# 17_Voltage_Regulators.net
KiCad netlist of a schematic drawn in Altium Designer
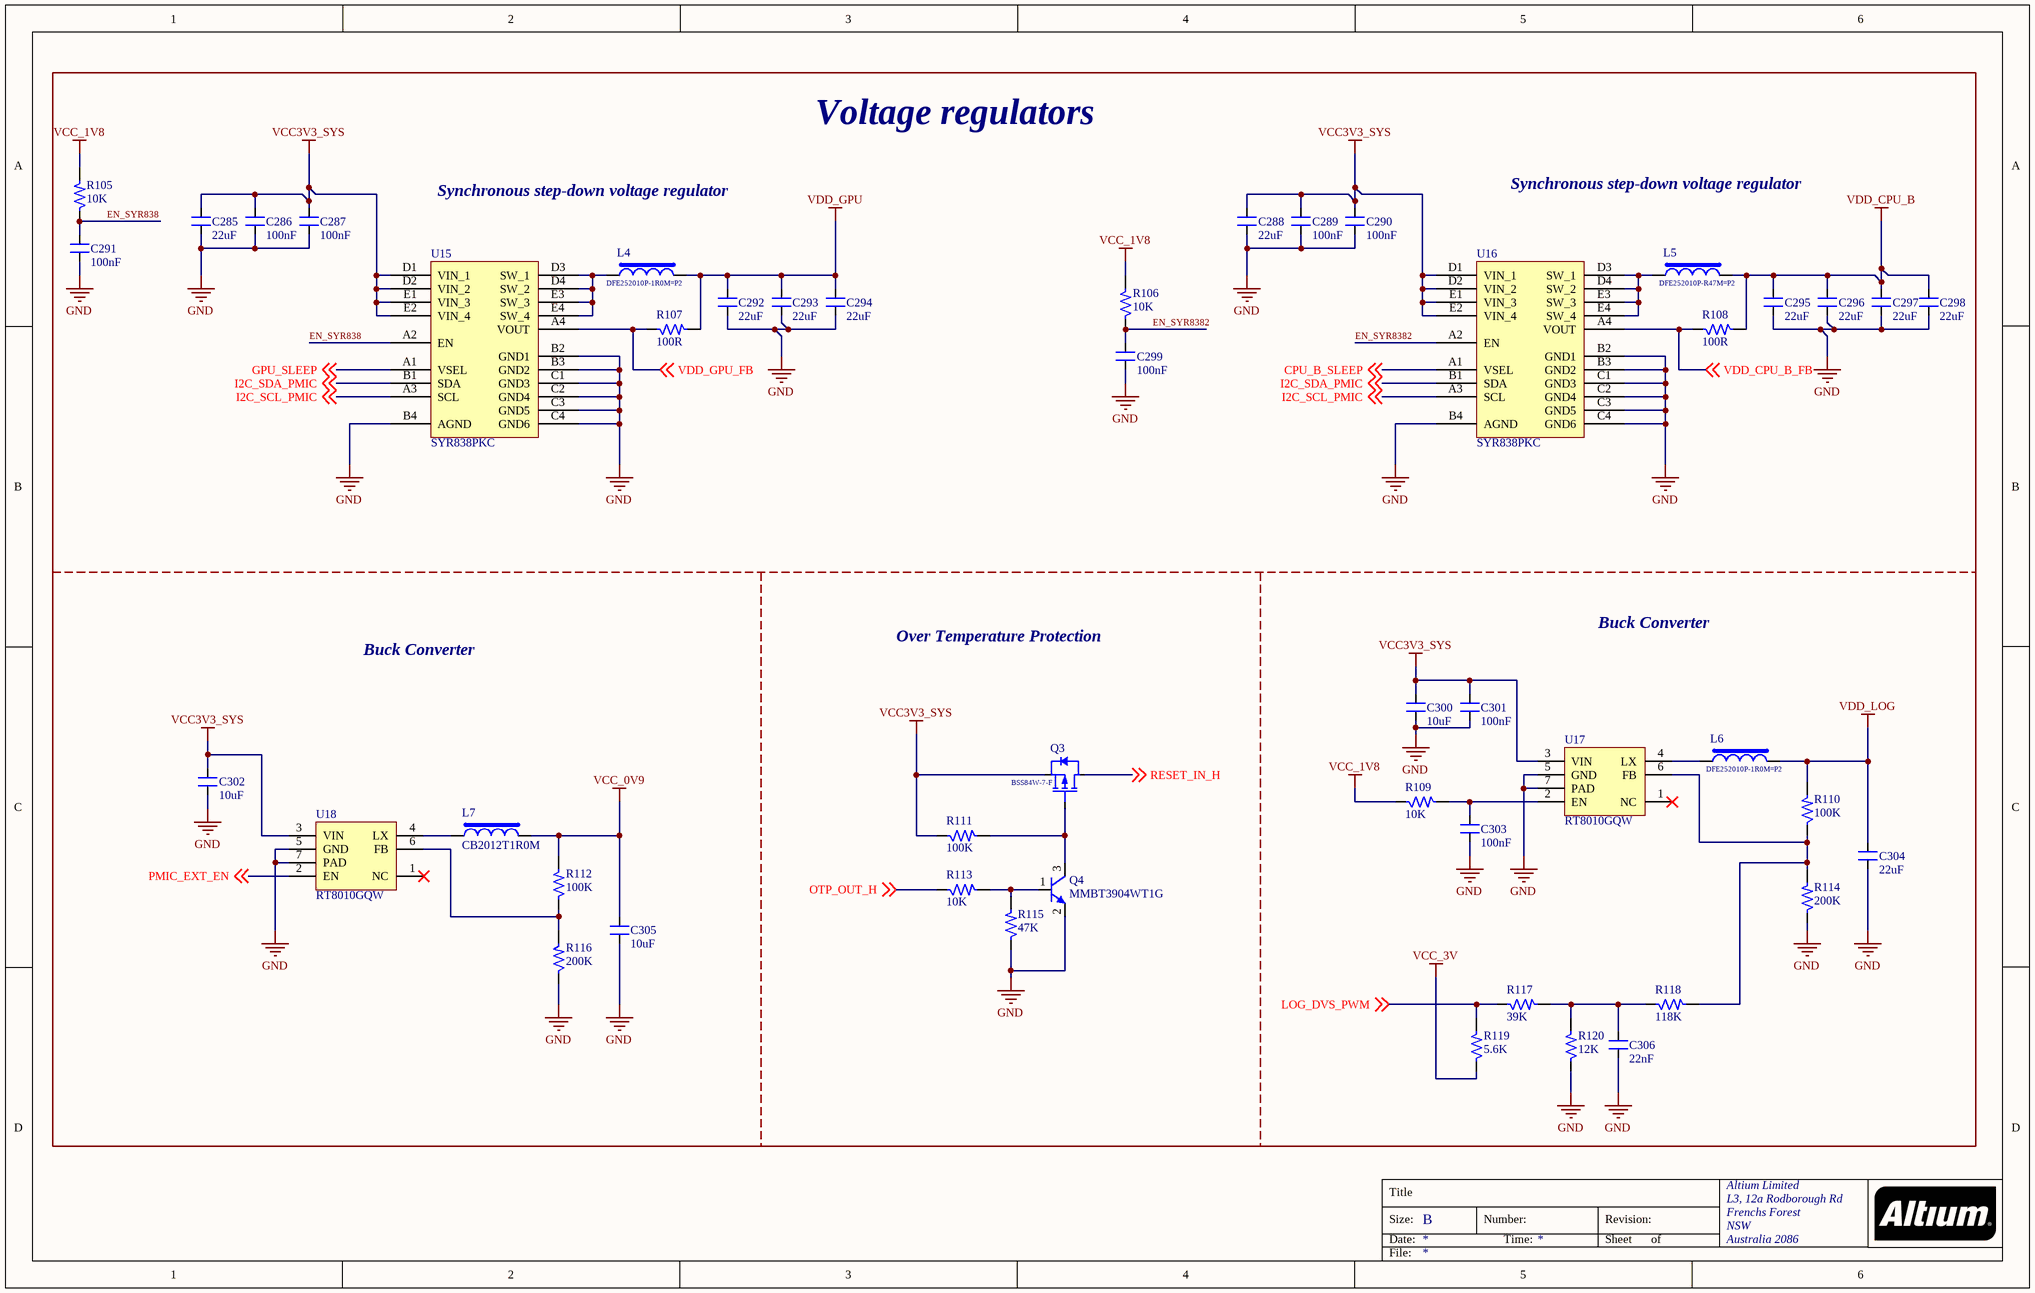
[diagram p0: [17] Voltage_Regulators.SchDoc]

(export (version "E")
  (design (tool "Eeschema 10.0.6"))
  (components
    (comp (ref "C285")
      (value "22uF")
      (footprint "CAP_0402")
      (description "22µF ±20% 6.3V Ceramic Capacitor X5R 0402 (1005 Metric)")
      (fields
        (field (name "MANUFACTURER") "Murata Electronics")
        (field (name "MANUFACTURER PART NUMBER") "CL05A226MQ5N6J8")
      )
      (libsource (lib "EsteemPCB_SOM_Course_intlib") (part "CAP_22uF-6.3V-20%-0402"))
    )
    (comp (ref "C286")
      (value "100nF")
      (footprint "CAP_0402")
      (description "0.1µF ±10% 25V Ceramic Capacitor X7R 0402 (1005 Metric)")
      (fields
        (field (name "MANUFACTURER") "Walsin Technology Corporation")
        (field (name "MANUFACTURER PART NUMBER") "0402B104K250CT")
      )
      (libsource (lib "EsteemPCB_SOM_Course_intlib") (part "CAP_100nF-25V-10%-0402"))
    )
    (comp (ref "C287")
      (value "100nF")
      (footprint "CAP_0402")
      (description "0.1µF ±10% 25V Ceramic Capacitor X7R 0402 (1005 Metric)")
      (fields
        (field (name "MANUFACTURER") "Walsin Technology Corporation")
        (field (name "MANUFACTURER PART NUMBER") "0402B104K250CT")
      )
      (libsource (lib "EsteemPCB_SOM_Course_intlib") (part "CAP_100nF-25V-10%-0402"))
    )
    (comp (ref "C288")
      (value "22uF")
      (footprint "CAP_0402")
      (description "22µF ±20% 6.3V Ceramic Capacitor X5R 0402 (1005 Metric)")
      (fields
        (field (name "MANUFACTURER") "Murata Electronics")
        (field (name "MANUFACTURER PART NUMBER") "CL05A226MQ5N6J8")
      )
      (libsource (lib "EsteemPCB_SOM_Course_intlib") (part "CAP_22uF-6.3V-20%-0402"))
    )
    (comp (ref "C289")
      (value "100nF")
      (footprint "CAP_0402")
      (description "0.1µF ±10% 25V Ceramic Capacitor X7R 0402 (1005 Metric)")
      (fields
        (field (name "MANUFACTURER") "Walsin Technology Corporation")
        (field (name "MANUFACTURER PART NUMBER") "0402B104K250CT")
      )
      (libsource (lib "EsteemPCB_SOM_Course_intlib") (part "CAP_100nF-25V-10%-0402"))
    )
    (comp (ref "C290")
      (value "100nF")
      (footprint "CAP_0402")
      (description "0.1µF ±10% 25V Ceramic Capacitor X7R 0402 (1005 Metric)")
      (fields
        (field (name "MANUFACTURER") "Walsin Technology Corporation")
        (field (name "MANUFACTURER PART NUMBER") "0402B104K250CT")
      )
      (libsource (lib "EsteemPCB_SOM_Course_intlib") (part "CAP_100nF-25V-10%-0402"))
    )
    (comp (ref "C291")
      (value "100nF")
      (footprint "CAP_0402")
      (description "0.1µF ±10% 25V Ceramic Capacitor X7R 0402 (1005 Metric)")
      (fields
        (field (name "MANUFACTURER") "Walsin Technology Corporation")
        (field (name "MANUFACTURER PART NUMBER") "0402B104K250CT")
      )
      (libsource (lib "EsteemPCB_SOM_Course_intlib") (part "CAP_100nF-25V-10%-0402"))
    )
    (comp (ref "C292")
      (value "22uF")
      (footprint "CAP_0402")
      (description "22µF ±20% 6.3V Ceramic Capacitor X5R 0402 (1005 Metric)")
      (fields
        (field (name "MANUFACTURER") "Murata Electronics")
        (field (name "MANUFACTURER PART NUMBER") "CL05A226MQ5N6J8")
      )
      (libsource (lib "EsteemPCB_SOM_Course_intlib") (part "CAP_22uF-6.3V-20%-0402"))
    )
    (comp (ref "C293")
      (value "22uF")
      (footprint "CAP_0402")
      (description "22µF ±20% 6.3V Ceramic Capacitor X5R 0402 (1005 Metric)")
      (fields
        (field (name "MANUFACTURER") "Murata Electronics")
        (field (name "MANUFACTURER PART NUMBER") "CL05A226MQ5N6J8")
      )
      (libsource (lib "EsteemPCB_SOM_Course_intlib") (part "CAP_22uF-6.3V-20%-0402"))
    )
    (comp (ref "C294")
      (value "22uF")
      (footprint "CAP_0402")
      (description "22µF ±20% 6.3V Ceramic Capacitor X5R 0402 (1005 Metric)")
      (fields
        (field (name "MANUFACTURER") "Murata Electronics")
        (field (name "MANUFACTURER PART NUMBER") "CL05A226MQ5N6J8")
      )
      (libsource (lib "EsteemPCB_SOM_Course_intlib") (part "CAP_22uF-6.3V-20%-0402"))
    )
    (comp (ref "C295")
      (value "22uF")
      (footprint "CAP_0402")
      (description "22µF ±20% 6.3V Ceramic Capacitor X5R 0402 (1005 Metric)")
      (fields
        (field (name "MANUFACTURER") "Murata Electronics")
        (field (name "MANUFACTURER PART NUMBER") "CL05A226MQ5N6J8")
      )
      (libsource (lib "EsteemPCB_SOM_Course_intlib") (part "CAP_22uF-6.3V-20%-0402"))
    )
    (comp (ref "C296")
      (value "22uF")
      (footprint "CAP_0402")
      (description "22µF ±20% 6.3V Ceramic Capacitor X5R 0402 (1005 Metric)")
      (fields
        (field (name "MANUFACTURER") "Murata Electronics")
        (field (name "MANUFACTURER PART NUMBER") "CL05A226MQ5N6J8")
      )
      (libsource (lib "EsteemPCB_SOM_Course_intlib") (part "CAP_22uF-6.3V-20%-0402"))
    )
    (comp (ref "C297")
      (value "22uF")
      (footprint "CAP_0402")
      (description "22µF ±20% 6.3V Ceramic Capacitor X5R 0402 (1005 Metric)")
      (fields
        (field (name "MANUFACTURER") "Murata Electronics")
        (field (name "MANUFACTURER PART NUMBER") "CL05A226MQ5N6J8")
      )
      (libsource (lib "EsteemPCB_SOM_Course_intlib") (part "CAP_22uF-6.3V-20%-0402"))
    )
    (comp (ref "C298")
      (value "22uF")
      (footprint "CAP_0402")
      (description "22µF ±20% 6.3V Ceramic Capacitor X5R 0402 (1005 Metric)")
      (fields
        (field (name "MANUFACTURER") "Murata Electronics")
        (field (name "MANUFACTURER PART NUMBER") "CL05A226MQ5N6J8")
      )
      (libsource (lib "EsteemPCB_SOM_Course_intlib") (part "CAP_22uF-6.3V-20%-0402"))
    )
    (comp (ref "C299")
      (value "100nF")
      (footprint "CAP_0402")
      (description "0.1µF ±10% 25V Ceramic Capacitor X7R 0402 (1005 Metric)")
      (fields
        (field (name "MANUFACTURER") "Walsin Technology Corporation")
        (field (name "MANUFACTURER PART NUMBER") "0402B104K250CT")
      )
      (libsource (lib "EsteemPCB_SOM_Course_intlib") (part "CAP_100nF-25V-10%-0402"))
    )
    (comp (ref "C300")
      (value "10uF")
      (footprint "CAP_0402")
      (description "10µF ±20% 10V Ceramic Capacitor X5R 0402 (1005 Metric)")
      (fields
        (field (name "MANUFACTURER PART NUMBER") "CL05A106MP5NUNC")
        (field (name "MANUFACTURER") "Samsung Electro-Mechanics")
      )
      (libsource (lib "EsteemPCB_SOM_Course_intlib") (part "CAP_10uF-10V-20%-0402"))
    )
    (comp (ref "C301")
      (value "100nF")
      (footprint "CAP_0402")
      (description "0.1µF ±10% 10V Ceramic Capacitor X7R 0402 (1005 Metric)")
      (fields
        (field (name "MANUFACTURER") "Yageo")
        (field (name "MANUFACTURER PART NUMBER") "CC0402KRX7R6BB104")
      )
      (libsource (lib "EsteemPCB_SOM_Course_intlib") (part "CAP_100nF-10V-10%-0402"))
    )
    (comp (ref "C302")
      (value "10uF")
      (footprint "CAP_0402")
      (description "10µF ±20% 10V Ceramic Capacitor X5R 0402 (1005 Metric)")
      (fields
        (field (name "MANUFACTURER PART NUMBER") "CL05A106MP5NUNC")
        (field (name "MANUFACTURER") "Samsung Electro-Mechanics")
      )
      (libsource (lib "EsteemPCB_SOM_Course_intlib") (part "CAP_10uF-10V-20%-0402"))
    )
    (comp (ref "C303")
      (value "100nF")
      (footprint "CAP_0402")
      (description "0.1µF ±10% 10V Ceramic Capacitor X7R 0402 (1005 Metric)")
      (fields
        (field (name "MANUFACTURER") "Yageo")
        (field (name "MANUFACTURER PART NUMBER") "CC0402KRX7R6BB104")
      )
      (libsource (lib "EsteemPCB_SOM_Course_intlib") (part "CAP_100nF-10V-10%-0402"))
    )
    (comp (ref "C304")
      (value "22uF")
      (footprint "CAP_0402")
      (description "22µF ±20% 6.3V Ceramic Capacitor X5R 0402 (1005 Metric)")
      (fields
        (field (name "MANUFACTURER") "Murata Electronics")
        (field (name "MANUFACTURER PART NUMBER") "CL05A226MQ5N6J8")
      )
      (libsource (lib "EsteemPCB_SOM_Course_intlib") (part "CAP_22uF-6.3V-20%-0402"))
    )
    (comp (ref "C305")
      (value "10uF")
      (footprint "CAP_0402")
      (description "10µF ±20% 10V Ceramic Capacitor X5R 0402 (1005 Metric)")
      (fields
        (field (name "MANUFACTURER PART NUMBER") "CL05A106MP5NUNC")
        (field (name "MANUFACTURER") "Samsung Electro-Mechanics")
      )
      (libsource (lib "EsteemPCB_SOM_Course_intlib") (part "CAP_10uF-10V-20%-0402"))
    )
    (comp (ref "C306")
      (value "22nF")
      (footprint "CAP_0402")
      (description "0.022µF ±10% 10V Ceramic Capacitor X7R 0402 (1005 Metric)")
      (fields
        (field (name "MANUFACTURER") "Samsung Electro-Mechanics")
        (field (name "MANUFACTURER PART NUMBER") "CL05B223KP5NNNC")
      )
      (libsource (lib "EsteemPCB_SOM_Course_intlib") (part "CAP_22nF-10V-10%-0402"))
    )
    (comp (ref "L4")
      (value "DFE252010P-1R0M=P2")
      (footprint "IND_1008")
      (description "1µH Shielded Wirewound Inductor 3.8A 54mOhm Max 1008 (2520 Metric)")
      (fields (field (name "MANUFACTURER") "Murata Electronics"))
      (libsource (lib "EsteemPCB_SOM_Course_intlib") (part "IND_1uH-3.8A-20%-1008"))
    )
    (comp (ref "L5")
      (value "DFE252010P-R47M=P2")
      (footprint "IND_1008")
      (description "470nH Shielded Wirewound Inductor 5A 35mOhm Max 1008 (2520 Metric)")
      (fields (field (name "MANUFACTURER") "Murata Electronics"))
      (libsource (lib "EsteemPCB_SOM_Course_intlib") (part "IND_470nH-5A-20%-1008"))
    )
    (comp (ref "L6")
      (value "DFE252010P-1R0M=P2")
      (footprint "IND_1008")
      (description "1µH Shielded Wirewound Inductor 3.8A 54mOhm Max 1008 (2520 Metric)")
      (fields (field (name "MANUFACTURER") "Murata Electronics"))
      (libsource (lib "EsteemPCB_SOM_Course_intlib") (part "IND_1uH-3.8A-20%-1008"))
    )
    (comp (ref "L7")
      (value "CB2012T1R0M")
      (footprint "IND_0805")
      (description "1uH ±20% 500mA 150mΩ 0805 Inductors (SMD) RoHS")
      (fields (field (name "MANUFACTURER") "Taiyo Yuden"))
      (libsource (lib "EsteemPCB_SOM_Course_intlib") (part "IND_1uF-0.5A-20%-0805"))
    )
    (comp (ref "Q3")
      (value "BSS84W-7-F")
      (footprint "SOT-323-3")
      (description "P-Channel 50V 130mA (Ta) 200mW (Ta) Surface Mount SOT-323")
      (fields (field (name "MANUFACTURER") "Diodes Incorporated"))
      (libsource (lib "EsteemPCB_SOM_Course_intlib") (part "MOSFET-P_50V-130mA-SOT-323"))
    )
    (comp (ref "Q4")
      (value "MMBT3904WT1G")
      (footprint "SOT-323-3")
      (description "Bipolar (BJT) Transistor NPN 40V 200mA 300MHz 150mW Surface Mount SC-70-3 (SOT323)")
      (fields (field (name "MANUFACTURER") "ON Semiconductor"))
      (libsource (lib "EsteemPCB_SOM_Course_intlib") (part "TRAN-NPN_40V-200mA-SOT323"))
    )
    (comp (ref "R105")
      (value "10K")
      (footprint "RES_0402")
      (description "10 kOhms ±1% 0.1W, 1/10W Chip Resistor 0402 (1005 Metric) Anti-Sulfur Thin Film")
      (fields
        (field (name "MANUFACTURER") "Vishay Beyschlag/Draloric/BC Components")
        (field (name "MANUFACTURER PART NUMBER") "MCS04020C1002FE000")
      )
      (libsource (lib "EsteemPCB_SOM_Course_intlib") (part "RES_10K-0.1W-1%-0402"))
    )
    (comp (ref "R106")
      (value "10K")
      (footprint "RES_0402")
      (description "10 kOhms ±1% 0.1W, 1/10W Chip Resistor 0402 (1005 Metric) Anti-Sulfur Thin Film")
      (fields
        (field (name "MANUFACTURER") "Vishay Beyschlag/Draloric/BC Components")
        (field (name "MANUFACTURER PART NUMBER") "MCS04020C1002FE000")
      )
      (libsource (lib "EsteemPCB_SOM_Course_intlib") (part "RES_10K-0.1W-1%-0402"))
    )
    (comp (ref "R107")
      (value "100R")
      (footprint "RES_0402")
      (fields
        (field (name "MANUFACTURER") "KOA Speer Electronics, Inc.")
        (field (name "MANUFACTURER PART NUMBER") "RK73H1ETTP1000F")
      )
      (libsource (lib "EsteemPCB_SOM_Course_intlib") (part "RES_100R-0.1W-1%-0402"))
    )
    (comp (ref "R108")
      (value "100R")
      (footprint "RES_0402")
      (fields
        (field (name "MANUFACTURER") "KOA Speer Electronics, Inc.")
        (field (name "MANUFACTURER PART NUMBER") "RK73H1ETTP1000F")
      )
      (libsource (lib "EsteemPCB_SOM_Course_intlib") (part "RES_100R-0.1W-1%-0402"))
    )
    (comp (ref "R109")
      (value "10K")
      (footprint "RES_0402")
      (description "10 kOhms ±1% 0.1W, 1/10W Chip Resistor 0402 (1005 Metric) Anti-Sulfur Thin Film")
      (fields
        (field (name "MANUFACTURER") "Vishay Beyschlag/Draloric/BC Components")
        (field (name "MANUFACTURER PART NUMBER") "MCS04020C1002FE000")
      )
      (libsource (lib "EsteemPCB_SOM_Course_intlib") (part "RES_10K-0.1W-1%-0402"))
    )
    (comp (ref "R110")
      (value "100K")
      (footprint "RES_0402")
      (description "100 kOhms ±1% 0.1W, 1/10W Chip Resistor 0402 (1005 Metric) Anti-Sulfur Thin Film")
      (fields
        (field (name "MANUFACTURER") "Vishay Beyschlag/Draloric/BC Components")
        (field (name "MANUFACTURER PART NUMBER") "MCS04020C1003FE000")
      )
      (libsource (lib "EsteemPCB_SOM_Course_intlib") (part "RES_100K-0.1W-1%-0402"))
    )
    (comp (ref "R111")
      (value "100K")
      (footprint "RES_0402")
      (description "100 kOhms ±1% 0.1W, 1/10W Chip Resistor 0402 (1005 Metric) Anti-Sulfur Thin Film")
      (fields
        (field (name "MANUFACTURER") "Vishay Beyschlag/Draloric/BC Components")
        (field (name "MANUFACTURER PART NUMBER") "MCS04020C1003FE000")
      )
      (libsource (lib "EsteemPCB_SOM_Course_intlib") (part "RES_100K-0.1W-1%-0402"))
    )
    (comp (ref "R112")
      (value "100K")
      (footprint "RES_0402")
      (description "100 kOhms ±1% 0.1W, 1/10W Chip Resistor 0402 (1005 Metric) Anti-Sulfur Thin Film")
      (fields
        (field (name "MANUFACTURER") "Vishay Beyschlag/Draloric/BC Components")
        (field (name "MANUFACTURER PART NUMBER") "MCS04020C1003FE000")
      )
      (libsource (lib "EsteemPCB_SOM_Course_intlib") (part "RES_100K-0.1W-1%-0402"))
    )
    (comp (ref "R113")
      (value "10K")
      (footprint "RES_0402")
      (description "10 kOhms ±1% 0.1W, 1/10W Chip Resistor 0402 (1005 Metric) Anti-Sulfur Thin Film")
      (fields
        (field (name "MANUFACTURER") "Vishay Beyschlag/Draloric/BC Components")
        (field (name "MANUFACTURER PART NUMBER") "MCS04020C1002FE000")
      )
      (libsource (lib "EsteemPCB_SOM_Course_intlib") (part "RES_10K-0.1W-1%-0402"))
    )
    (comp (ref "R114")
      (value "200K")
      (footprint "RES_0402")
      (description "200 kOhms ±1% 0.1W, 1/10W Chip Resistor 0402 (1005 Metric) Automotive AEC-Q200 Thick Film")
      (fields
        (field (name "MANUFACTURER") "Panasonic Electronic Components")
        (field (name "MANUFACTURER PART NUMBER") "ERJ-2RKF2003X")
      )
      (libsource (lib "EsteemPCB_SOM_Course_intlib") (part "RES_200K-0.1W-1%-0402"))
    )
    (comp (ref "R115")
      (value "47K")
      (footprint "RES_0402")
      (description "47 kOhms ±1% 0.1W, 1/10W Chip Resistor 0402 (1005 Metric) Automotive AEC-Q200 Thick Film")
      (fields
        (field (name "MANUFACTURER") "Panasonic Electronic Components")
        (field (name "MANUFACTURER PART NUMBER") "ERJ-2RKF4702X")
      )
      (libsource (lib "EsteemPCB_SOM_Course_intlib") (part "RES_47K-0.1W-1%-0402"))
    )
    (comp (ref "R116")
      (value "200K")
      (footprint "RES_0402")
      (description "200 kOhms ±1% 0.1W, 1/10W Chip Resistor 0402 (1005 Metric) Automotive AEC-Q200 Thick Film")
      (fields
        (field (name "MANUFACTURER") "Panasonic Electronic Components")
        (field (name "MANUFACTURER PART NUMBER") "ERJ-2RKF2003X")
      )
      (libsource (lib "EsteemPCB_SOM_Course_intlib") (part "RES_200K-0.1W-1%-0402"))
    )
    (comp (ref "R117")
      (value "39K")
      (footprint "RES_0402")
      (fields
        (field (name "MANUFACTURER") "KOA Speer Electronics, Inc.")
        (field (name "MANUFACTURER PART NUMBER") "RK73H1ETTP3902F")
      )
      (libsource (lib "EsteemPCB_SOM_Course_intlib") (part "RES_39K-0.1W-1%-0402"))
    )
    (comp (ref "R118")
      (value "118K")
      (footprint "RES_0402")
      (fields
        (field (name "MANUFACTURER") "KOA Speer Electronics, Inc.")
        (field (name "MANUAFCTURER PART NUMBER") "RK73H1ETTP1183F")
      )
      (libsource (lib "EsteemPCB_SOM_Course_intlib") (part "RES_118K-0.1W-1%-0402"))
    )
    (comp (ref "R119")
      (value "5.6K")
      (footprint "RES_0402")
      (fields
        (field (name "MANUFACTURER") "KOA Speer Electronics, Inc.")
        (field (name "MANUFACTURER PART NUMBER") "RK73H1ETTP5601F")
      )
      (libsource (lib "EsteemPCB_SOM_Course_intlib") (part "RES_5.6K-0.1W-1%-0402"))
    )
    (comp (ref "R120")
      (value "12K")
      (footprint "RES_0402")
      (description "12 kOhms ±1% 0.1W, 1/10W Chip Resistor 0402 (1005 Metric) Anti-Sulfur Thin Film")
      (fields
        (field (name "MANUFACTURER") "Vishay Beyschlag/Draloric/BC Components")
        (field (name "MANUFACTURER PART NUMBER") "MCS04020C1202FE000")
      )
      (libsource (lib "EsteemPCB_SOM_Course_intlib") (part "RES_12K-0.1W-1%-0402"))
    )
    (comp (ref "U15")
      (value "SYR838PKC")
      (footprint "CSP20_15.7_100x84_SMD")
      (description "Step-Down Positive Programmable 1 6A 2.4MHz CSP1.56*1.96-20 DC-DC Converters RoHS")
      (fields (field (name "MANUFACTURER") "Silergy Corp"))
      (libsource (lib "EsteemPCB_SOM_Course_intlib") (part "IC_SYR838PKC"))
    )
    (comp (ref "U16")
      (value "SYR838PKC")
      (footprint "CSP20_15.7_100x84_SMD")
      (description "Step-Down Positive Programmable 1 6A 2.4MHz CSP1.56*1.96-20 DC-DC Converters RoHS")
      (fields (field (name "MANUFACTURER") "Silergy Corp"))
      (libsource (lib "EsteemPCB_SOM_Course_intlib") (part "IC_SYR838PKC"))
    )
    (comp (ref "U17")
      (value "RT8010GQW")
      (footprint "WDFN-6_26_133X100_SMD")
      (description "Buck Switching Regulator IC Positive Adjustable 0.6V 1 Output 1A 6-WDFN Exposed Pad")
      (fields (field (name "MANUFACTURER") "Richtek USA Inc."))
      (libsource (lib "EsteemPCB_SOM_Course_intlib") (part "REG-ADJ_5.5V-5.5V-1A-6-WDFN"))
    )
    (comp (ref "U18")
      (value "RT8010GQW")
      (footprint "WDFN-6_26_133X100_SMD")
      (description "Buck Switching Regulator IC Positive Adjustable 0.6V 1 Output 1A 6-WDFN Exposed Pad")
      (fields (field (name "MANUFACTURER") "Richtek USA Inc."))
      (libsource (lib "EsteemPCB_SOM_Course_intlib") (part "REG-ADJ_5.5V-5.5V-1A-6-WDFN"))
    )
  )
  (nets
    (net (code "1") (name "/EN_SYR838") (class "Default")
      (node (ref "C291") (pin "2") (pinfunction "2_2") (pintype "passive"))
      (node (ref "R105") (pin "1") (pinfunction "1_1") (pintype "passive"))
      (node (ref "U15") (pin "A2") (pinfunction "EN_A2") (pintype "passive"))
    )
    (net (code "2") (name "/EN_SYR8382") (class "Default")
      (node (ref "C299") (pin "2") (pinfunction "2_2") (pintype "passive"))
      (node (ref "R106") (pin "1") (pinfunction "1_1") (pintype "passive"))
      (node (ref "U16") (pin "A2") (pinfunction "EN_A2") (pintype "passive"))
    )
    (net (code "3") (name "CPU_B_SLEEP") (class "Default")
      (node (ref "U16") (pin "A1") (pinfunction "VSEL_A1") (pintype "passive"))
    )
    (net (code "4") (name "GND") (class "Default")
      (node (ref "C285") (pin "1") (pinfunction "1_1") (pintype "passive"))
      (node (ref "C286") (pin "1") (pinfunction "1_1") (pintype "passive"))
      (node (ref "C287") (pin "1") (pinfunction "1_1") (pintype "passive"))
      (node (ref "C288") (pin "1") (pinfunction "1_1") (pintype "passive"))
      (node (ref "C289") (pin "1") (pinfunction "1_1") (pintype "passive"))
      (node (ref "C290") (pin "1") (pinfunction "1_1") (pintype "passive"))
      (node (ref "C291") (pin "1") (pinfunction "1_1") (pintype "passive"))
      (node (ref "C292") (pin "1") (pinfunction "1_1") (pintype "passive"))
      (node (ref "C293") (pin "1") (pinfunction "1_1") (pintype "passive"))
      (node (ref "C294") (pin "1") (pinfunction "1_1") (pintype "passive"))
      (node (ref "C295") (pin "1") (pinfunction "1_1") (pintype "passive"))
      (node (ref "C296") (pin "1") (pinfunction "1_1") (pintype "passive"))
      (node (ref "C297") (pin "1") (pinfunction "1_1") (pintype "passive"))
      (node (ref "C298") (pin "1") (pinfunction "1_1") (pintype "passive"))
      (node (ref "C299") (pin "1") (pinfunction "1_1") (pintype "passive"))
      (node (ref "C300") (pin "1") (pinfunction "1_1") (pintype "passive"))
      (node (ref "C301") (pin "1") (pinfunction "1_1") (pintype "passive"))
      (node (ref "C302") (pin "1") (pinfunction "1_1") (pintype "passive"))
      (node (ref "C303") (pin "1") (pinfunction "1_1") (pintype "passive"))
      (node (ref "C304") (pin "1") (pinfunction "1_1") (pintype "passive"))
      (node (ref "C305") (pin "1") (pinfunction "1_1") (pintype "passive"))
      (node (ref "C306") (pin "1") (pinfunction "1_1") (pintype "passive"))
      (node (ref "Q4") (pin "2") (pinfunction "E_2") (pintype "passive"))
      (node (ref "R114") (pin "1") (pinfunction "1_1") (pintype "passive"))
      (node (ref "R115") (pin "1") (pinfunction "1_1") (pintype "passive"))
      (node (ref "R116") (pin "1") (pinfunction "1_1") (pintype "passive"))
      (node (ref "R120") (pin "1") (pinfunction "1_1") (pintype "passive"))
      (node (ref "U15") (pin "B2") (pinfunction "GND1_B2") (pintype "passive"))
      (node (ref "U15") (pin "B3") (pinfunction "GND2_B3") (pintype "passive"))
      (node (ref "U15") (pin "B4") (pinfunction "AGND_B4") (pintype "passive"))
      (node (ref "U15") (pin "C1") (pinfunction "GND3_C1") (pintype "passive"))
      (node (ref "U15") (pin "C2") (pinfunction "GND4_C2") (pintype "passive"))
      (node (ref "U15") (pin "C3") (pinfunction "GND5_C3") (pintype "passive"))
      (node (ref "U15") (pin "C4") (pinfunction "GND6_C4") (pintype "passive"))
      (node (ref "U16") (pin "B2") (pinfunction "GND1_B2") (pintype "passive"))
      (node (ref "U16") (pin "B3") (pinfunction "GND2_B3") (pintype "passive"))
      (node (ref "U16") (pin "B4") (pinfunction "AGND_B4") (pintype "passive"))
      (node (ref "U16") (pin "C1") (pinfunction "GND3_C1") (pintype "passive"))
      (node (ref "U16") (pin "C2") (pinfunction "GND4_C2") (pintype "passive"))
      (node (ref "U16") (pin "C3") (pinfunction "GND5_C3") (pintype "passive"))
      (node (ref "U16") (pin "C4") (pinfunction "GND6_C4") (pintype "passive"))
      (node (ref "U17") (pin "5") (pinfunction "GND_5") (pintype "passive"))
      (node (ref "U17") (pin "7") (pinfunction "PAD_7") (pintype "passive"))
      (node (ref "U18") (pin "5") (pinfunction "GND_5") (pintype "passive"))
      (node (ref "U18") (pin "7") (pinfunction "PAD_7") (pintype "passive"))
    )
    (net (code "5") (name "GPU_SLEEP") (class "Default")
      (node (ref "U15") (pin "A1") (pinfunction "VSEL_A1") (pintype "passive"))
    )
    (net (code "6") (name "I2C_SCL_PMIC") (class "Default")
      (node (ref "U15") (pin "A3") (pinfunction "SCL_A3") (pintype "passive"))
      (node (ref "U16") (pin "A3") (pinfunction "SCL_A3") (pintype "passive"))
    )
    (net (code "7") (name "I2C_SDA_PMIC") (class "Default")
      (node (ref "U15") (pin "B1") (pinfunction "SDA_B1") (pintype "passive"))
      (node (ref "U16") (pin "B1") (pinfunction "SDA_B1") (pintype "passive"))
    )
    (net (code "8") (name "LOG_DVS_PWM") (class "Default")
      (node (ref "R117") (pin "1") (pinfunction "1_1") (pintype "passive"))
      (node (ref "R119") (pin "2") (pinfunction "2_2") (pintype "passive"))
    )
    (net (code "9") (name "Net-(C306-Pad2)") (class "Default")
      (node (ref "C306") (pin "2") (pinfunction "2_2") (pintype "passive"))
      (node (ref "R117") (pin "2") (pinfunction "2_2") (pintype "passive"))
      (node (ref "R118") (pin "1") (pinfunction "1_1") (pintype "passive"))
      (node (ref "R120") (pin "2") (pinfunction "2_2") (pintype "passive"))
    )
    (net (code "10") (name "Net-(Q3-G)") (class "Default")
      (node (ref "Q3") (pin "1") (pinfunction "G_1") (pintype "passive"))
      (node (ref "Q4") (pin "3") (pinfunction "C_3") (pintype "passive"))
      (node (ref "R111") (pin "2") (pinfunction "2_2") (pintype "passive"))
    )
    (net (code "11") (name "Net-(Q4-B)") (class "Default")
      (node (ref "Q4") (pin "1") (pinfunction "B_1") (pintype "passive"))
      (node (ref "R113") (pin "2") (pinfunction "2_2") (pintype "passive"))
      (node (ref "R115") (pin "2") (pinfunction "2_2") (pintype "passive"))
    )
    (net (code "12") (name "Net-(U15-SW_1)") (class "Default")
      (node (ref "L4") (pin "1") (pinfunction "1_1") (pintype "passive"))
      (node (ref "U15") (pin "D3") (pinfunction "SW_1_D3") (pintype "passive"))
      (node (ref "U15") (pin "D4") (pinfunction "SW_2_D4") (pintype "passive"))
      (node (ref "U15") (pin "E3") (pinfunction "SW_3_E3") (pintype "passive"))
      (node (ref "U15") (pin "E4") (pinfunction "SW_4_E4") (pintype "passive"))
    )
    (net (code "13") (name "Net-(U16-SW_1)") (class "Default")
      (node (ref "L5") (pin "1") (pinfunction "1_1") (pintype "passive"))
      (node (ref "U16") (pin "D3") (pinfunction "SW_1_D3") (pintype "passive"))
      (node (ref "U16") (pin "D4") (pinfunction "SW_2_D4") (pintype "passive"))
      (node (ref "U16") (pin "E3") (pinfunction "SW_3_E3") (pintype "passive"))
      (node (ref "U16") (pin "E4") (pinfunction "SW_4_E4") (pintype "passive"))
    )
    (net (code "14") (name "Net-(U17-EN)") (class "Default")
      (node (ref "C303") (pin "2") (pinfunction "2_2") (pintype "passive"))
      (node (ref "R109") (pin "2") (pinfunction "2_2") (pintype "passive"))
      (node (ref "U17") (pin "2") (pinfunction "EN_2") (pintype "passive"))
    )
    (net (code "15") (name "Net-(U17-FB)") (class "Default")
      (node (ref "R110") (pin "1") (pinfunction "1_1") (pintype "passive"))
      (node (ref "R114") (pin "2") (pinfunction "2_2") (pintype "passive"))
      (node (ref "R118") (pin "2") (pinfunction "2_2") (pintype "passive"))
      (node (ref "U17") (pin "6") (pinfunction "FB_6") (pintype "passive"))
    )
    (net (code "16") (name "Net-(U17-LX)") (class "Default")
      (node (ref "L6") (pin "1") (pinfunction "1_1") (pintype "passive"))
      (node (ref "U17") (pin "4") (pinfunction "LX_4") (pintype "passive"))
    )
    (net (code "17") (name "Net-(U18-FB)") (class "Default")
      (node (ref "R112") (pin "1") (pinfunction "1_1") (pintype "passive"))
      (node (ref "R116") (pin "2") (pinfunction "2_2") (pintype "passive"))
      (node (ref "U18") (pin "6") (pinfunction "FB_6") (pintype "passive"))
    )
    (net (code "18") (name "Net-(U18-LX)") (class "Default")
      (node (ref "L7") (pin "1") (pinfunction "1_1") (pintype "passive"))
      (node (ref "U18") (pin "4") (pinfunction "LX_4") (pintype "passive"))
    )
    (net (code "19") (name "OTP_OUT_H") (class "Default")
      (node (ref "R113") (pin "1") (pinfunction "1_1") (pintype "passive"))
    )
    (net (code "20") (name "PMIC_EXT_EN") (class "Default")
      (node (ref "U18") (pin "2") (pinfunction "EN_2") (pintype "passive"))
    )
    (net (code "21") (name "RESET_IN_H") (class "Default")
      (node (ref "Q3") (pin "3") (pinfunction "D_3") (pintype "passive"))
    )
    (net (code "22") (name "VCC3V3_SYS") (class "Default")
      (node (ref "C285") (pin "2") (pinfunction "2_2") (pintype "passive"))
      (node (ref "C286") (pin "2") (pinfunction "2_2") (pintype "passive"))
      (node (ref "C287") (pin "2") (pinfunction "2_2") (pintype "passive"))
      (node (ref "C288") (pin "2") (pinfunction "2_2") (pintype "passive"))
      (node (ref "C289") (pin "2") (pinfunction "2_2") (pintype "passive"))
      (node (ref "C290") (pin "2") (pinfunction "2_2") (pintype "passive"))
      (node (ref "C300") (pin "2") (pinfunction "2_2") (pintype "passive"))
      (node (ref "C301") (pin "2") (pinfunction "2_2") (pintype "passive"))
      (node (ref "C302") (pin "2") (pinfunction "2_2") (pintype "passive"))
      (node (ref "Q3") (pin "2") (pinfunction "S_2") (pintype "passive"))
      (node (ref "R111") (pin "1") (pinfunction "1_1") (pintype "passive"))
      (node (ref "U15") (pin "D1") (pinfunction "VIN_1_D1") (pintype "passive"))
      (node (ref "U15") (pin "D2") (pinfunction "VIN_2_D2") (pintype "passive"))
      (node (ref "U15") (pin "E1") (pinfunction "VIN_3_E1") (pintype "passive"))
      (node (ref "U15") (pin "E2") (pinfunction "VIN_4_E2") (pintype "passive"))
      (node (ref "U16") (pin "D1") (pinfunction "VIN_1_D1") (pintype "passive"))
      (node (ref "U16") (pin "D2") (pinfunction "VIN_2_D2") (pintype "passive"))
      (node (ref "U16") (pin "E1") (pinfunction "VIN_3_E1") (pintype "passive"))
      (node (ref "U16") (pin "E2") (pinfunction "VIN_4_E2") (pintype "passive"))
      (node (ref "U17") (pin "3") (pinfunction "VIN_3") (pintype "passive"))
      (node (ref "U18") (pin "3") (pinfunction "VIN_3") (pintype "passive"))
    )
    (net (code "23") (name "VCC_0V9") (class "Default")
      (node (ref "C305") (pin "2") (pinfunction "2_2") (pintype "passive"))
      (node (ref "L7") (pin "2") (pinfunction "2_2") (pintype "passive"))
      (node (ref "R112") (pin "2") (pinfunction "2_2") (pintype "passive"))
    )
    (net (code "24") (name "VCC_1V8") (class "Default")
      (node (ref "R105") (pin "2") (pinfunction "2_2") (pintype "passive"))
      (node (ref "R106") (pin "2") (pinfunction "2_2") (pintype "passive"))
      (node (ref "R109") (pin "1") (pinfunction "1_1") (pintype "passive"))
    )
    (net (code "25") (name "VCC_3V") (class "Default")
      (node (ref "R119") (pin "1") (pinfunction "1_1") (pintype "passive"))
    )
    (net (code "26") (name "VDD_CPU_B") (class "Default")
      (node (ref "C295") (pin "2") (pinfunction "2_2") (pintype "passive"))
      (node (ref "C296") (pin "2") (pinfunction "2_2") (pintype "passive"))
      (node (ref "C297") (pin "2") (pinfunction "2_2") (pintype "passive"))
      (node (ref "C298") (pin "2") (pinfunction "2_2") (pintype "passive"))
      (node (ref "L5") (pin "2") (pinfunction "2_2") (pintype "passive"))
      (node (ref "R108") (pin "2") (pinfunction "2_2") (pintype "passive"))
    )
    (net (code "27") (name "VDD_CPU_B_FB") (class "Default")
      (node (ref "R108") (pin "1") (pinfunction "1_1") (pintype "passive"))
      (node (ref "U16") (pin "A4") (pinfunction "VOUT_A4") (pintype "passive"))
    )
    (net (code "28") (name "VDD_GPU") (class "Default")
      (node (ref "C292") (pin "2") (pinfunction "2_2") (pintype "passive"))
      (node (ref "C293") (pin "2") (pinfunction "2_2") (pintype "passive"))
      (node (ref "C294") (pin "2") (pinfunction "2_2") (pintype "passive"))
      (node (ref "L4") (pin "2") (pinfunction "2_2") (pintype "passive"))
      (node (ref "R107") (pin "2") (pinfunction "2_2") (pintype "passive"))
    )
    (net (code "29") (name "VDD_GPU_FB") (class "Default")
      (node (ref "R107") (pin "1") (pinfunction "1_1") (pintype "passive"))
      (node (ref "U15") (pin "A4") (pinfunction "VOUT_A4") (pintype "passive"))
    )
    (net (code "30") (name "VDD_LOG") (class "Default")
      (node (ref "C304") (pin "2") (pinfunction "2_2") (pintype "passive"))
      (node (ref "L6") (pin "2") (pinfunction "2_2") (pintype "passive"))
      (node (ref "R110") (pin "2") (pinfunction "2_2") (pintype "passive"))
    )
    (net (code "31") (name "unconnected-(U17-NC-Pad1)") (class "Default")
      (node (ref "U17") (pin "1") (pinfunction "NC_1") (pintype "passive+no_connect"))
    )
    (net (code "32") (name "unconnected-(U18-NC-Pad1)") (class "Default")
      (node (ref "U18") (pin "1") (pinfunction "NC_1") (pintype "passive+no_connect"))
    )
  )
)
